# quadparts.net
KiCad netlist of a schematic drawn in EAGLE
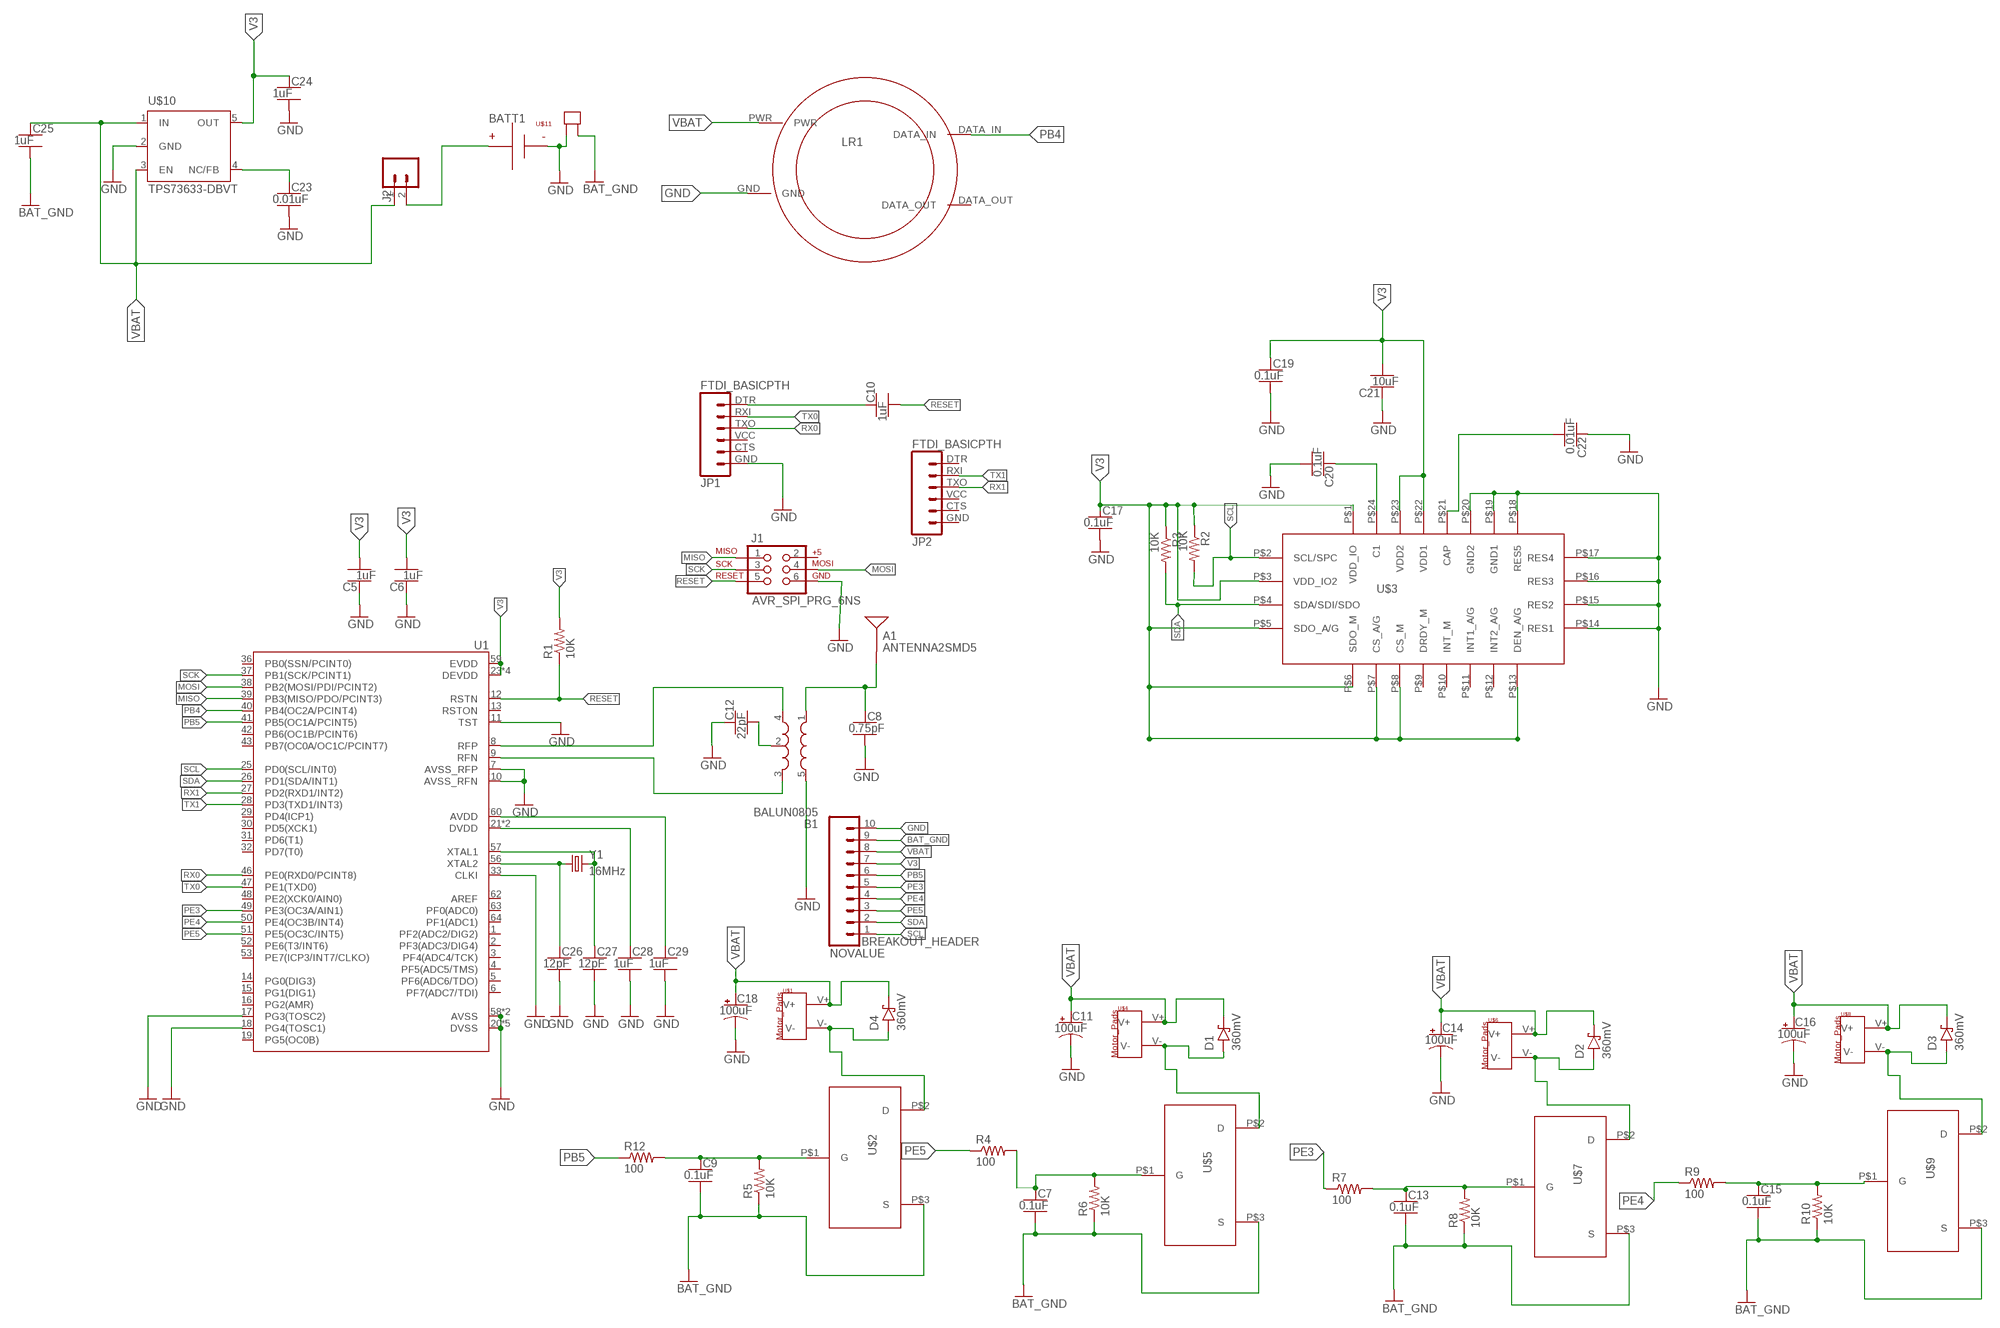
[diagram p0: schematic, sheet 1]

(export (version "E")
  (design (tool "Eeschema 10.0.6"))
  (components
    (comp (ref "A1")
      (value "ANTENNA2SMD5")
      (footprint "eagle-import:ANTENNA-CHIP5")
      (fields (field (name "MFR") "Linx Technologies Inc.") (field (name "MPN") "ANT-2.45-CHP-T"))
      (libsource (lib "eagle-import") (part "ANTENNA2SMD5"))
    )
    (comp (ref "B1")
      (value "BALUN0805")
      (footprint "eagle-import:BALUN")
      (fields (field (name "MFR") "Wurth Electronics Inc") (field (name "MPN") "748421245"))
      (libsource (lib "eagle-import") (part "BALUN0805"))
    )
    (comp (ref "BATT1")
      (value "BATTERY-HUBSAN-W/HOLDER")
      (footprint "eagle-import:BATTERY-W_HOLDER-380MAH-HUBSAN")
      (fields
        (field (name "MFR") "HUBSAN")
        (field (name "MPN") "X4-H107C-8-in-1")
        (field (name "CREATOR") "Swanson")
      )
      (libsource (lib "eagle-import") (part "BATTERY-HUBSAN-W/HOLDER"))
    )
    (comp (ref "BREAKOUT_HEADER")
      (value "NOVALUE")
      (footprint "eagle-import:HDRV10W63P254_10X1_2540X254H838_HS")
      (fields (field (name "MFR") "Amphenol FCI") (field (name "MPN") "68000-110HLF"))
      (libsource (lib "eagle-import") (part "SIP-10_TH-254X10"))
    )
    (comp (ref "C5")
      (value "1uF")
      (footprint "eagle-import:CAPC2012X140_HS")
      (fields
        (field (name "MFR") "Murata Electronics North America")
        (field (name "MPN") "GRM21BR71H105KA12L")
      )
      (libsource (lib "eagle-import") (part "CAPACITOR-NP_SMD-2012-0805_CERAMIC-1UF"))
    )
    (comp (ref "C6")
      (value "1uF")
      (footprint "eagle-import:CAPC2012X140_HS")
      (fields
        (field (name "MFR") "Murata Electronics North America")
        (field (name "MPN") "GRM21BR71H105KA12L")
      )
      (libsource (lib "eagle-import") (part "CAPACITOR-NP_SMD-2012-0805_CERAMIC-1UF"))
    )
    (comp (ref "C7")
      (value "0.1uF")
      (footprint "eagle-import:CERAMIC_CAP_0805")
      (fields
        (field (name "MFR") "Murata Electronics North America")
        (field (name "MPN") "GRM21BR71H104KA01L")
        (field (name "CREATOR") "SWANSON")
      )
      (libsource (lib "eagle-import") (part "CERAMIC_CAP-0805-0.1UF"))
    )
    (comp (ref "C8")
      (value "0.75pF")
      (footprint "eagle-import:CAPC2012X140_HS")
      (fields
        (field (name "MFR") "Murata Electronics North America")
        (field (name "MPN") "GQM2195C2AR75CB01D")
      )
      (libsource (lib "eagle-import") (part "CAPACITOR-NP_SMD-2012-0805_CERAMIC-0.75PF"))
    )
    (comp (ref "C9")
      (value "0.1uF")
      (footprint "eagle-import:CERAMIC_CAP_0805")
      (fields
        (field (name "MFR") "Murata Electronics North America")
        (field (name "MPN") "GRM21BR71H104KA01L")
        (field (name "CREATOR") "SWANSON")
      )
      (libsource (lib "eagle-import") (part "CERAMIC_CAP-0805-0.1UF"))
    )
    (comp (ref "C10")
      (value "1uF")
      (footprint "eagle-import:CAPC2012X140_HS")
      (fields
        (field (name "MFR") "Murata Electronics North America")
        (field (name "MPN") "GRM21BR71H105KA12L")
      )
      (libsource (lib "eagle-import") (part "CAPACITOR-NP_SMD-2012-0805_CERAMIC-1UF"))
    )
    (comp (ref "C11")
      (value "100uF")
      (footprint "eagle-import:CAPMP7343X310_HS")
      (fields (field (name "MFR") "AVX Corporation") (field (name "MPN") "TAJD227K006RNJ"))
      (libsource (lib "eagle-import") (part "CAPACITOR-POL_SMD-7043-D_TANTALUM-220UF"))
    )
    (comp (ref "C12")
      (value "22pF")
      (footprint "eagle-import:CAPC2012X140_HS")
      (fields
        (field (name "MFR") "Murata Electronics North America")
        (field (name "MPN") "GRM21A5C2E220JW01D")
      )
      (libsource (lib "eagle-import") (part "CAPACITOR-NP_SMD-2012-0805_CERAMIC-22PF"))
    )
    (comp (ref "C13")
      (value "0.1uF")
      (footprint "eagle-import:CERAMIC_CAP_0805")
      (fields
        (field (name "MFR") "Murata Electronics North America")
        (field (name "MPN") "GRM21BR71H104KA01L")
        (field (name "CREATOR") "SWANSON")
      )
      (libsource (lib "eagle-import") (part "CERAMIC_CAP-0805-0.1UF"))
    )
    (comp (ref "C14")
      (value "100uF")
      (footprint "eagle-import:CAPMP7343X310_HS")
      (fields (field (name "MFR") "AVX Corporation") (field (name "MPN") "TAJD227K006RNJ"))
      (libsource (lib "eagle-import") (part "CAPACITOR-POL_SMD-7043-D_TANTALUM-220UF"))
    )
    (comp (ref "C15")
      (value "0.1uF")
      (footprint "eagle-import:CERAMIC_CAP_0805")
      (fields
        (field (name "MFR") "Murata Electronics North America")
        (field (name "MPN") "GRM21BR71H104KA01L")
        (field (name "CREATOR") "SWANSON")
      )
      (libsource (lib "eagle-import") (part "CERAMIC_CAP-0805-0.1UF"))
    )
    (comp (ref "C16")
      (value "100uF")
      (footprint "eagle-import:CAPMP7343X310_HS")
      (fields (field (name "MFR") "AVX Corporation") (field (name "MPN") "TAJD227K006RNJ"))
      (libsource (lib "eagle-import") (part "CAPACITOR-POL_SMD-7043-D_TANTALUM-220UF"))
    )
    (comp (ref "C17")
      (value "0.1uF")
      (footprint "eagle-import:CAPC2012X140_HS")
      (fields
        (field (name "MFR") "Murata Electronics North America")
        (field (name "MPN") "GRM21BR71H104KA01L")
      )
      (libsource (lib "eagle-import") (part "CAPACITOR-NP_SMD-2012-0805_CERAMIC-0.1UF"))
    )
    (comp (ref "C18")
      (value "100uF")
      (footprint "eagle-import:CAPMP7343X310_HS")
      (fields (field (name "MFR") "AVX Corporation") (field (name "MPN") "TAJD227K006RNJ"))
      (libsource (lib "eagle-import") (part "CAPACITOR-POL_SMD-7043-D_TANTALUM-220UF"))
    )
    (comp (ref "C19")
      (value "0.1uF")
      (footprint "eagle-import:CAPC2012X140_HS")
      (fields
        (field (name "MFR") "Murata Electronics North America")
        (field (name "MPN") "GRM21BR71H104KA01L")
      )
      (libsource (lib "eagle-import") (part "CAPACITOR-NP_SMD-2012-0805_CERAMIC-0.1UF"))
    )
    (comp (ref "C20")
      (value "0.1uF")
      (footprint "eagle-import:CAPC2012X140_HS")
      (fields
        (field (name "MFR") "Murata Electronics North America")
        (field (name "MPN") "GRM21BR71H104KA01L")
      )
      (libsource (lib "eagle-import") (part "CAPACITOR-NP_SMD-2012-0805_CERAMIC-0.1UF"))
    )
    (comp (ref "C21")
      (value "10uF")
      (footprint "eagle-import:CAPC2012X140_HS")
      (fields
        (field (name "MFR") "Murata Electronics North America")
        (field (name "MPN") "GRM21BR61E106KA73L")
      )
      (libsource (lib "eagle-import") (part "CAPACITOR-NP_SMD-2012-0805_CERAMIC-10UF"))
    )
    (comp (ref "C22")
      (value "0.01uF")
      (footprint "eagle-import:CAPC2012X140_HS")
      (fields
        (field (name "MFR") "Murata Electronics North America")
        (field (name "MPN") "GRM2195C1H103FA01D")
      )
      (libsource (lib "eagle-import") (part "CAPACITOR-NP_SMD-2012-0805_CERAMIC-0.01UF"))
    )
    (comp (ref "C23")
      (value "0.01uF")
      (footprint "eagle-import:CAPC2012X140_HS")
      (fields
        (field (name "MFR") "Murata Electronics North America")
        (field (name "MPN") "GRM2195C1H103FA01D")
      )
      (libsource (lib "eagle-import") (part "CAPACITOR-NP_SMD-2012-0805_CERAMIC-0.01UF"))
    )
    (comp (ref "C24")
      (value "1uF")
      (footprint "eagle-import:CAPC2012X140_HS")
      (fields
        (field (name "MFR") "Murata Electronics North America")
        (field (name "MPN") "GRM21BR71H105KA12L")
      )
      (libsource (lib "eagle-import") (part "CAPACITOR-NP_SMD-2012-0805_CERAMIC-1UF"))
    )
    (comp (ref "C25")
      (value "1uF")
      (footprint "eagle-import:CAPC2012X140_HS")
      (fields
        (field (name "MFR") "Murata Electronics North America")
        (field (name "MPN") "GRM21BR71H105KA12L")
      )
      (libsource (lib "eagle-import") (part "CAPACITOR-NP_SMD-2012-0805_CERAMIC-1UF"))
    )
    (comp (ref "C26")
      (value "12pF")
      (footprint "eagle-import:CAPC2012X140_HS")
      (fields
        (field (name "MFR") "Murata Electronics North America")
        (field (name "MPN") "GRM21A5C2E120JW01D")
      )
      (libsource (lib "eagle-import") (part "CAPACITOR-NP_SMD-2012-0805_CERAMIC-12PF"))
    )
    (comp (ref "C27")
      (value "12pF")
      (footprint "eagle-import:CAPC2012X140_HS")
      (fields
        (field (name "MFR") "Murata Electronics North America")
        (field (name "MPN") "GRM21A5C2E120JW01D")
      )
      (libsource (lib "eagle-import") (part "CAPACITOR-NP_SMD-2012-0805_CERAMIC-12PF"))
    )
    (comp (ref "C28")
      (value "1uF")
      (footprint "eagle-import:CAPC2012X140_HS")
      (fields
        (field (name "MFR") "Murata Electronics North America")
        (field (name "MPN") "GRM21BR71H105KA12L")
      )
      (libsource (lib "eagle-import") (part "CAPACITOR-NP_SMD-2012-0805_CERAMIC-1UF"))
    )
    (comp (ref "C29")
      (value "1uF")
      (footprint "eagle-import:CAPC2012X140_HS")
      (fields
        (field (name "MFR") "Murata Electronics North America")
        (field (name "MPN") "GRM21BR71H105KA12L")
      )
      (libsource (lib "eagle-import") (part "CAPACITOR-NP_SMD-2012-0805_CERAMIC-1UF"))
    )
    (comp (ref "D1")
      (value "360mV")
      (footprint "eagle-import:SOD3716X135_HS")
      (fields
        (field (name "MFR") "Toshiba Semiconductor and Storage")
        (field (name "MPN") "CRS08(TE85L,Q,M)")
      )
      (libsource (lib "eagle-import") (part "DIODE-SCHOTTKY_SMD-SOD123-360MV"))
    )
    (comp (ref "D2")
      (value "360mV")
      (footprint "eagle-import:SOD3716X135_HS")
      (fields
        (field (name "MFR") "Toshiba Semiconductor and Storage")
        (field (name "MPN") "CRS08(TE85L,Q,M)")
      )
      (libsource (lib "eagle-import") (part "DIODE-SCHOTTKY_SMD-SOD123-360MV"))
    )
    (comp (ref "D3")
      (value "360mV")
      (footprint "eagle-import:SOD3716X135_HS")
      (fields
        (field (name "MFR") "Toshiba Semiconductor and Storage")
        (field (name "MPN") "CRS08(TE85L,Q,M)")
      )
      (libsource (lib "eagle-import") (part "DIODE-SCHOTTKY_SMD-SOD123-360MV"))
    )
    (comp (ref "D4")
      (value "360mV")
      (footprint "eagle-import:SOD3716X135_HS")
      (fields
        (field (name "MFR") "Toshiba Semiconductor and Storage")
        (field (name "MPN") "CRS08(TE85L,Q,M)")
      )
      (libsource (lib "eagle-import") (part "DIODE-SCHOTTKY_SMD-SOD123-360MV"))
    )
    (comp (ref "J1")
      (value "AVR_SPI_PRG_6NS")
      (footprint "eagle-import:2X3-NS")
      (fields (field (name "MFR") "Amphenol FCI") (field (name "MPN") "67997-206HLF"))
      (libsource (lib "eagle-import") (part "AVR_SPI_PRG_6NS"))
    )
    (comp (ref "J2")
      (value "MALE_HEADER_2POS-2X1-0.1IN")
      (footprint "eagle-import:MALE_HEADER_2X1_0.1IN")
      (fields
        (field (name "MFR") "3M")
        (field (name "MPN") "961102-6404-AR")
        (field (name "CREATOR") "SWANSON")
      )
      (libsource (lib "eagle-import") (part "MALE_HEADER_2POS-2X1-0.1IN"))
    )
    (comp (ref "JP1")
      (value "FTDI_BASICPTH")
      (footprint "eagle-import:FTDI_BASIC")
      (fields (field (name "MFR") "Amphenol FCI") (field (name "MPN") "68016-406HLF"))
      (libsource (lib "eagle-import") (part "FTDI_BASICPTH"))
    )
    (comp (ref "JP2")
      (value "FTDI_BASICPTH")
      (footprint "eagle-import:FTDI_BASIC")
      (fields (field (name "MFR") "Amphenol FCI") (field (name "MPN") "68016-406HLF"))
      (libsource (lib "eagle-import") (part "FTDI_BASICPTH"))
    )
    (comp (ref "LR1")
      (value "LED_RING")
      (footprint "eagle-import:LED_RING")
      (libsource (lib "eagle-import") (part "LED_RING"))
    )
    (comp (ref "R1")
      (value "10K")
      (footprint "eagle-import:RESC2012X60_HS")
      (fields (field (name "MFR") "Yageo") (field (name "MPN") "RC0805JR-0710KL"))
      (libsource (lib "eagle-import") (part "RESISTOR_SMD-2012-0805-10K"))
    )
    (comp (ref "R2")
      (value "10K")
      (footprint "eagle-import:RESC2012X60_HS")
      (fields (field (name "MFR") "Yageo") (field (name "MPN") "RC0805JR-0710KL"))
      (libsource (lib "eagle-import") (part "RESISTOR_SMD-2012-0805-10K"))
    )
    (comp (ref "R3")
      (value "10K")
      (footprint "eagle-import:RESC2012X60_HS")
      (fields (field (name "MFR") "Yageo") (field (name "MPN") "RC0805JR-0710KL"))
      (libsource (lib "eagle-import") (part "RESISTOR_SMD-2012-0805-10K"))
    )
    (comp (ref "R4")
      (value "100")
      (footprint "eagle-import:RESC2012X60_HS")
      (fields (field (name "MFR") "Yageo") (field (name "MPN") "RC0805JR-07100RL"))
      (libsource (lib "eagle-import") (part "RESISTOR_SMD-2012-0805-100"))
    )
    (comp (ref "R5")
      (value "10K")
      (footprint "eagle-import:RESC2012X60_HS")
      (fields (field (name "MFR") "Yageo") (field (name "MPN") "RC0805JR-0710KL"))
      (libsource (lib "eagle-import") (part "RESISTOR_SMD-2012-0805-10K"))
    )
    (comp (ref "R6")
      (value "10K")
      (footprint "eagle-import:RESC2012X60_HS")
      (fields (field (name "MFR") "Yageo") (field (name "MPN") "RC0805JR-0710KL"))
      (libsource (lib "eagle-import") (part "RESISTOR_SMD-2012-0805-10K"))
    )
    (comp (ref "R7")
      (value "100")
      (footprint "eagle-import:RESC2012X60_HS")
      (fields (field (name "MFR") "Yageo") (field (name "MPN") "RC0805JR-07100RL"))
      (libsource (lib "eagle-import") (part "RESISTOR_SMD-2012-0805-100"))
    )
    (comp (ref "R8")
      (value "10K")
      (footprint "eagle-import:RESC2012X60_HS")
      (fields (field (name "MFR") "Yageo") (field (name "MPN") "RC0805JR-0710KL"))
      (libsource (lib "eagle-import") (part "RESISTOR_SMD-2012-0805-10K"))
    )
    (comp (ref "R9")
      (value "100")
      (footprint "eagle-import:RESC2012X60_HS")
      (fields (field (name "MFR") "Yageo") (field (name "MPN") "RC0805JR-07100RL"))
      (libsource (lib "eagle-import") (part "RESISTOR_SMD-2012-0805-100"))
    )
    (comp (ref "R10")
      (value "10K")
      (footprint "eagle-import:RESC2012X60_HS")
      (fields (field (name "MFR") "Yageo") (field (name "MPN") "RC0805JR-0710KL"))
      (libsource (lib "eagle-import") (part "RESISTOR_SMD-2012-0805-10K"))
    )
    (comp (ref "R12")
      (value "100")
      (footprint "eagle-import:RESC2012X60_HS")
      (fields (field (name "MFR") "Yageo") (field (name "MPN") "RC0805JR-07100RL"))
      (libsource (lib "eagle-import") (part "RESISTOR_SMD-2012-0805-100"))
    )
    (comp (ref "U$1")
      (value "MOTOR_PADS")
      (footprint "eagle-import:MOTOR_PADS")
      (fields (field (name "MFR") "NA"))
      (libsource (lib "eagle-import") (part "MOTOR_PADS"))
    )
    (comp (ref "U$2")
      (value "N-CHANNEL_MOSFET")
      (footprint "eagle-import:N-CHANNELMOFSET")
      (fields
        (field (name "MFR") "Vishay Siliconix")
        (field (name "MPN") "SI2302CDS-T1-E3")
        (field (name "CREATOR") "Jason_Wong")
      )
      (libsource (lib "eagle-import") (part "N-CHANNEL_MOSFET"))
    )
    (comp (ref "U$3")
      (value "9-AXIS_IMU")
      (footprint "eagle-import:9-AXIS_IMU")
      (fields
        (field (name "MFR") "STMicroelectronics")
        (field (name "MPN") "LSM9DS1TR")
        (field (name "CREATOR") "Jason_Wong")
      )
      (libsource (lib "eagle-import") (part "9-AXIS_IMU"))
    )
    (comp (ref "U$4")
      (value "MOTOR_PADS")
      (footprint "eagle-import:MOTOR_PADS")
      (fields (field (name "MFR") "NA"))
      (libsource (lib "eagle-import") (part "MOTOR_PADS"))
    )
    (comp (ref "U$5")
      (value "N-CHANNEL_MOSFET")
      (footprint "eagle-import:N-CHANNELMOFSET")
      (fields
        (field (name "MFR") "Vishay Siliconix")
        (field (name "MPN") "SI2302CDS-T1-E3")
        (field (name "CREATOR") "Jason_Wong")
      )
      (libsource (lib "eagle-import") (part "N-CHANNEL_MOSFET"))
    )
    (comp (ref "U$6")
      (value "MOTOR_PADS")
      (footprint "eagle-import:MOTOR_PADS")
      (fields (field (name "MFR") "NA"))
      (libsource (lib "eagle-import") (part "MOTOR_PADS"))
    )
    (comp (ref "U$7")
      (value "N-CHANNEL_MOSFET")
      (footprint "eagle-import:N-CHANNELMOFSET")
      (fields
        (field (name "MFR") "Vishay Siliconix")
        (field (name "MPN") "SI2302CDS-T1-E3")
        (field (name "CREATOR") "Jason_Wong")
      )
      (libsource (lib "eagle-import") (part "N-CHANNEL_MOSFET"))
    )
    (comp (ref "U$8")
      (value "MOTOR_PADS")
      (footprint "eagle-import:MOTOR_PADS")
      (fields (field (name "MFR") "NA"))
      (libsource (lib "eagle-import") (part "MOTOR_PADS"))
    )
    (comp (ref "U$9")
      (value "N-CHANNEL_MOSFET")
      (footprint "eagle-import:N-CHANNELMOFSET")
      (fields
        (field (name "MFR") "Vishay Siliconix")
        (field (name "MPN") "SI2302CDS-T1-E3")
        (field (name "CREATOR") "Jason_Wong")
      )
      (libsource (lib "eagle-import") (part "N-CHANNEL_MOSFET"))
    )
    (comp (ref "U$10")
      (value "TPS73633-DBVT")
      (footprint "eagle-import:SOT23-DBV")
      (fields (field (name "MFR") "Texas Instruments") (field (name "MPN") "LP3985IM5X-3.0/NOPB"))
      (libsource (lib "eagle-import") (part "TPS73633-DBVT"))
    )
    (comp (ref "U$11")
      (value "NET_BRIDGE")
      (footprint "eagle-import:NET_BRIDGE")
      (libsource (lib "eagle-import") (part "NET_BRIDGE"))
    )
    (comp (ref "U1")
      (value "ATMEGA128RFA1")
      (footprint "eagle-import:QFN-64")
      (fields
        (field (name "MFR") "Atmel")
        (field (name "MPN") "ATMEGA128RFA1-ZUR00")
        (field (name "CREATOR") "Swanson")
      )
      (libsource (lib "eagle-import") (part "ATMEGA128RFA1"))
    )
    (comp (ref "Y1")
      (value "16MHz")
      (footprint "eagle-import:CRYSTAL-SMD-5X3")
      (fields (field (name "MFR") "Abracon LLC") (field (name "MPN") "ABM3B-16.000MHZ-B2-T"))
      (libsource (lib "eagle-import") (part "CRYSTAL5X3"))
    )
  )
  (nets
    (net (code "1") (name "BAT_GND") (class "Default")
      (node (ref "BREAKOUT_HEADER") (pin "9") (pinfunction "9_9") (pintype "passive"))
      (node (ref "C13") (pin "2") (pinfunction "2_2") (pintype "passive"))
      (node (ref "C15") (pin "2") (pinfunction "2_2") (pintype "passive"))
      (node (ref "C25") (pin "2") (pinfunction "2_2") (pintype "passive"))
      (node (ref "C7") (pin "2") (pinfunction "2_2") (pintype "passive"))
      (node (ref "C9") (pin "2") (pinfunction "2_2") (pintype "passive"))
      (node (ref "R10") (pin "1") (pinfunction "1_1") (pintype "passive"))
      (node (ref "R5") (pin "1") (pinfunction "1_1") (pintype "passive"))
      (node (ref "R6") (pin "1") (pinfunction "1_1") (pintype "passive"))
      (node (ref "R8") (pin "1") (pinfunction "1_1") (pintype "passive"))
      (node (ref "U$11") (pin "P$2") (pinfunction "P$2_P$2") (pintype "bidirectional"))
      (node (ref "U$2") (pin "P$3") (pinfunction "S_P$3") (pintype "bidirectional"))
      (node (ref "U$5") (pin "P$3") (pinfunction "S_P$3") (pintype "bidirectional"))
      (node (ref "U$7") (pin "P$3") (pinfunction "S_P$3") (pintype "bidirectional"))
      (node (ref "U$9") (pin "P$3") (pinfunction "S_P$3") (pintype "bidirectional"))
    )
    (net (code "2") (name "GND") (class "Default")
      (node (ref "B1") (pin "5") (pinfunction "GND_5") (pintype "bidirectional"))
      (node (ref "BATT1") (pin "-") (pinfunction "N_-") (pintype "bidirectional"))
      (node (ref "BREAKOUT_HEADER") (pin "10") (pinfunction "10_10") (pintype "passive"))
      (node (ref "C11") (pin "2") (pinfunction "-_2") (pintype "passive"))
      (node (ref "C12") (pin "1") (pinfunction "1_1") (pintype "passive"))
      (node (ref "C14") (pin "2") (pinfunction "-_2") (pintype "passive"))
      (node (ref "C16") (pin "2") (pinfunction "-_2") (pintype "passive"))
      (node (ref "C17") (pin "2") (pinfunction "2_2") (pintype "passive"))
      (node (ref "C18") (pin "2") (pinfunction "-_2") (pintype "passive"))
      (node (ref "C19") (pin "2") (pinfunction "2_2") (pintype "passive"))
      (node (ref "C20") (pin "2") (pinfunction "2_2") (pintype "passive"))
      (node (ref "C21") (pin "1") (pinfunction "1_1") (pintype "passive"))
      (node (ref "C22") (pin "1") (pinfunction "1_1") (pintype "passive"))
      (node (ref "C23") (pin "2") (pinfunction "2_2") (pintype "passive"))
      (node (ref "C24") (pin "2") (pinfunction "2_2") (pintype "passive"))
      (node (ref "C26") (pin "2") (pinfunction "2_2") (pintype "passive"))
      (node (ref "C27") (pin "2") (pinfunction "2_2") (pintype "passive"))
      (node (ref "C28") (pin "2") (pinfunction "2_2") (pintype "passive"))
      (node (ref "C29") (pin "2") (pinfunction "2_2") (pintype "passive"))
      (node (ref "C5") (pin "1") (pinfunction "1_1") (pintype "passive"))
      (node (ref "C6") (pin "1") (pinfunction "1_1") (pintype "passive"))
      (node (ref "C8") (pin "2") (pinfunction "2_2") (pintype "passive"))
      (node (ref "J1") (pin "6") (pinfunction "6_6") (pintype "passive"))
      (node (ref "JP1") (pin "GND") (pinfunction "6_GND") (pintype "passive"))
      (node (ref "LR1") (pin "GND") (pinfunction "GND_GND") (pintype "bidirectional"))
      (node (ref "U$10") (pin "2") (pinfunction "GND_2") (pintype "input"))
      (node (ref "U$11") (pin "P$1") (pinfunction "P$1_P$1") (pintype "bidirectional"))
      (node (ref "U$3") (pin "P$14") (pinfunction "RES1_P$14") (pintype "bidirectional"))
      (node (ref "U$3") (pin "P$15") (pinfunction "RES2_P$15") (pintype "bidirectional"))
      (node (ref "U$3") (pin "P$16") (pinfunction "RES3_P$16") (pintype "bidirectional"))
      (node (ref "U$3") (pin "P$17") (pinfunction "RES4_P$17") (pintype "bidirectional"))
      (node (ref "U$3") (pin "P$18") (pinfunction "RES5_P$18") (pintype "bidirectional"))
      (node (ref "U$3") (pin "P$19") (pinfunction "GND1_P$19") (pintype "bidirectional"))
      (node (ref "U$3") (pin "P$20") (pinfunction "GND2_P$20") (pintype "bidirectional"))
      (node (ref "U1") (pin "10") (pinfunction "AVSS_RFN_10") (pintype "bidirectional"))
      (node (ref "U1") (pin "11") (pinfunction "TST_11") (pintype "bidirectional"))
      (node (ref "U1") (pin "17") (pinfunction "PG3(TOSC2)_17") (pintype "bidirectional"))
      (node (ref "U1") (pin "18") (pinfunction "PG4(TOSC1)_18") (pintype "bidirectional"))
      (node (ref "U1") (pin "20") (pinfunction "DVSS_20") (pintype "bidirectional"))
      (node (ref "U1") (pin "24") (pinfunction "DVSS_24") (pintype "bidirectional"))
      (node (ref "U1") (pin "33") (pinfunction "CLKI_33") (pintype "bidirectional"))
      (node (ref "U1") (pin "35") (pinfunction "DVSS_35") (pintype "bidirectional"))
      (node (ref "U1") (pin "45") (pinfunction "DVSS_45") (pintype "bidirectional"))
      (node (ref "U1") (pin "55") (pinfunction "DVSS_55") (pintype "bidirectional"))
      (node (ref "U1") (pin "58") (pinfunction "AVSS_58") (pintype "bidirectional"))
      (node (ref "U1") (pin "61") (pinfunction "AVSS_61") (pintype "bidirectional"))
      (node (ref "U1") (pin "7") (pinfunction "AVSS_RFP_7") (pintype "bidirectional"))
    )
    (net (code "3") (name "MISO") (class "Default")
      (node (ref "J1") (pin "1") (pinfunction "1_1") (pintype "passive"))
      (node (ref "U1") (pin "39") (pinfunction "PB3(MISO/PDO/PCINT3)_39") (pintype "bidirectional"))
    )
    (net (code "4") (name "MOSI") (class "Default")
      (node (ref "J1") (pin "4") (pinfunction "4_4") (pintype "passive"))
      (node (ref "U1") (pin "38") (pinfunction "PB2(MOSI/PDI/PCINT2)_38") (pintype "bidirectional"))
    )
    (net (code "5") (name "Net-(A1-SIGNAL)") (class "Default")
      (node (ref "A1") (pin "FEED") (pinfunction "SIGNAL_FEED") (pintype "bidirectional"))
      (node (ref "B1") (pin "1") (pinfunction "IN_1") (pintype "bidirectional"))
      (node (ref "C8") (pin "1") (pinfunction "1_1") (pintype "passive"))
    )
    (net (code "6") (name "Net-(B1-GND-Pad2)") (class "Default")
      (node (ref "B1") (pin "2") (pinfunction "GND_2") (pintype "bidirectional"))
      (node (ref "C12") (pin "2") (pinfunction "2_2") (pintype "passive"))
    )
    (net (code "7") (name "Net-(B1-OUT1)") (class "Default")
      (node (ref "B1") (pin "4") (pinfunction "OUT1_4") (pintype "bidirectional"))
      (node (ref "U1") (pin "8") (pinfunction "RFP_8") (pintype "bidirectional"))
    )
    (net (code "8") (name "Net-(B1-OUT2)") (class "Default")
      (node (ref "B1") (pin "3") (pinfunction "OUT2_3") (pintype "bidirectional"))
      (node (ref "U1") (pin "9") (pinfunction "RFN_9") (pintype "bidirectional"))
    )
    (net (code "9") (name "Net-(BATT1-P)") (class "Default")
      (node (ref "BATT1") (pin "+") (pinfunction "P_+") (pintype "bidirectional"))
      (node (ref "J2") (pin "2") (pinfunction "2_2") (pintype "passive"))
    )
    (net (code "10") (name "Net-(C16-+)") (class "Default")
      (node (ref "C16") (pin "1") (pinfunction "+_1") (pintype "passive"))
      (node (ref "D3") (pin "C") (pinfunction "C_C") (pintype "passive"))
      (node (ref "U$8") (pin "V+") (pinfunction "V+_V+") (pintype "bidirectional"))
    )
    (net (code "11") (name "Net-(C28-Pad1)") (class "Default")
      (node (ref "C28") (pin "1") (pinfunction "1_1") (pintype "passive"))
      (node (ref "U1") (pin "21") (pinfunction "DVDD_21") (pintype "bidirectional"))
      (node (ref "U1") (pin "22") (pinfunction "DVDD_22") (pintype "bidirectional"))
    )
    (net (code "12") (name "Net-(JP1-1)") (class "Default")
      (node (ref "C10") (pin "1") (pinfunction "1_1") (pintype "passive"))
      (node (ref "JP1") (pin "DTR") (pinfunction "1_DTR") (pintype "passive"))
    )
    (net (code "13") (name "Net-(U$2-D)") (class "Default")
      (node (ref "D4") (pin "A") (pinfunction "A_A") (pintype "passive"))
      (node (ref "U$1") (pin "V-") (pinfunction "V-_V-") (pintype "bidirectional"))
      (node (ref "U$2") (pin "P$2") (pinfunction "D_P$2") (pintype "bidirectional"))
    )
    (net (code "14") (name "Net-(U$2-G)") (class "Default")
      (node (ref "C9") (pin "1") (pinfunction "1_1") (pintype "passive"))
      (node (ref "R12") (pin "2") (pinfunction "2_2") (pintype "passive"))
      (node (ref "R5") (pin "2") (pinfunction "2_2") (pintype "passive"))
      (node (ref "U$2") (pin "P$1") (pinfunction "G_P$1") (pintype "bidirectional"))
    )
    (net (code "15") (name "Net-(U$3-C1)") (class "Default")
      (node (ref "C20") (pin "1") (pinfunction "1_1") (pintype "passive"))
      (node (ref "U$3") (pin "P$24") (pinfunction "C1_P$24") (pintype "bidirectional"))
    )
    (net (code "16") (name "Net-(U$3-CAP)") (class "Default")
      (node (ref "C22") (pin "2") (pinfunction "2_2") (pintype "passive"))
      (node (ref "U$3") (pin "P$21") (pinfunction "CAP_P$21") (pintype "bidirectional"))
    )
    (net (code "17") (name "Net-(U$5-D)") (class "Default")
      (node (ref "D1") (pin "A") (pinfunction "A_A") (pintype "passive"))
      (node (ref "U$4") (pin "V-") (pinfunction "V-_V-") (pintype "bidirectional"))
      (node (ref "U$5") (pin "P$2") (pinfunction "D_P$2") (pintype "bidirectional"))
    )
    (net (code "18") (name "Net-(U$5-G)") (class "Default")
      (node (ref "C7") (pin "1") (pinfunction "1_1") (pintype "passive"))
      (node (ref "R4") (pin "2") (pinfunction "2_2") (pintype "passive"))
      (node (ref "R6") (pin "2") (pinfunction "2_2") (pintype "passive"))
      (node (ref "U$5") (pin "P$1") (pinfunction "G_P$1") (pintype "bidirectional"))
    )
    (net (code "19") (name "Net-(U$7-D)") (class "Default")
      (node (ref "D2") (pin "A") (pinfunction "A_A") (pintype "passive"))
      (node (ref "U$6") (pin "V-") (pinfunction "V-_V-") (pintype "bidirectional"))
      (node (ref "U$7") (pin "P$2") (pinfunction "D_P$2") (pintype "bidirectional"))
    )
    (net (code "20") (name "Net-(U$7-G)") (class "Default")
      (node (ref "C13") (pin "1") (pinfunction "1_1") (pintype "passive"))
      (node (ref "R7") (pin "2") (pinfunction "2_2") (pintype "passive"))
      (node (ref "R8") (pin "2") (pinfunction "2_2") (pintype "passive"))
      (node (ref "U$7") (pin "P$1") (pinfunction "G_P$1") (pintype "bidirectional"))
    )
    (net (code "21") (name "Net-(U$9-D)") (class "Default")
      (node (ref "D3") (pin "A") (pinfunction "A_A") (pintype "passive"))
      (node (ref "U$8") (pin "V-") (pinfunction "V-_V-") (pintype "bidirectional"))
      (node (ref "U$9") (pin "P$2") (pinfunction "D_P$2") (pintype "bidirectional"))
    )
    (net (code "22") (name "Net-(U$9-G)") (class "Default")
      (node (ref "C15") (pin "1") (pinfunction "1_1") (pintype "passive"))
      (node (ref "R10") (pin "2") (pinfunction "2_2") (pintype "passive"))
      (node (ref "R9") (pin "2") (pinfunction "2_2") (pintype "passive"))
      (node (ref "U$9") (pin "P$1") (pinfunction "G_P$1") (pintype "bidirectional"))
    )
    (net (code "23") (name "Net-(U$10-NC{slash}FB)") (class "Default")
      (node (ref "C23") (pin "1") (pinfunction "1_1") (pintype "passive"))
      (node (ref "U$10") (pin "4") (pinfunction "NC/FB_4") (pintype "passive"))
    )
    (net (code "24") (name "Net-(U1-AVDD)") (class "Default")
      (node (ref "C29") (pin "1") (pinfunction "1_1") (pintype "passive"))
      (node (ref "U1") (pin "60") (pinfunction "AVDD_60") (pintype "bidirectional"))
    )
    (net (code "25") (name "Net-(U1-XTAL1)") (class "Default")
      (node (ref "C27") (pin "1") (pinfunction "1_1") (pintype "passive"))
      (node (ref "U1") (pin "57") (pinfunction "XTAL1_57") (pintype "bidirectional"))
      (node (ref "Y1") (pin "3") (pinfunction "2_3") (pintype "passive"))
    )
    (net (code "26") (name "Net-(U1-XTAL2)") (class "Default")
      (node (ref "C26") (pin "1") (pinfunction "1_1") (pintype "passive"))
      (node (ref "U1") (pin "56") (pinfunction "XTAL2_56") (pintype "bidirectional"))
      (node (ref "Y1") (pin "1") (pinfunction "1_1") (pintype "passive"))
    )
    (net (code "27") (name "PB4") (class "Default")
      (node (ref "LR1") (pin "DATA_IN") (pinfunction "DATA_IN_DATA_IN") (pintype "bidirectional"))
      (node (ref "U1") (pin "40") (pinfunction "PB4(OC2A/PCINT4)_40") (pintype "bidirectional"))
    )
    (net (code "28") (name "PB5") (class "Default")
      (node (ref "BREAKOUT_HEADER") (pin "6") (pinfunction "6_6") (pintype "passive"))
      (node (ref "R12") (pin "1") (pinfunction "1_1") (pintype "passive"))
      (node (ref "U1") (pin "41") (pinfunction "PB5(OC1A/PCINT5)_41") (pintype "bidirectional"))
    )
    (net (code "29") (name "PE3") (class "Default")
      (node (ref "BREAKOUT_HEADER") (pin "5") (pinfunction "5_5") (pintype "passive"))
      (node (ref "R7") (pin "1") (pinfunction "1_1") (pintype "passive"))
      (node (ref "U1") (pin "49") (pinfunction "PE3(OC3A/AIN1)_49") (pintype "bidirectional"))
    )
    (net (code "30") (name "PE4") (class "Default")
      (node (ref "BREAKOUT_HEADER") (pin "4") (pinfunction "4_4") (pintype "passive"))
      (node (ref "R9") (pin "1") (pinfunction "1_1") (pintype "passive"))
      (node (ref "U1") (pin "50") (pinfunction "PE4(OC3B/INT4)_50") (pintype "bidirectional"))
    )
    (net (code "31") (name "PE5") (class "Default")
      (node (ref "BREAKOUT_HEADER") (pin "3") (pinfunction "3_3") (pintype "passive"))
      (node (ref "R4") (pin "1") (pinfunction "1_1") (pintype "passive"))
      (node (ref "U1") (pin "51") (pinfunction "PE5(OC3C/INT5)_51") (pintype "bidirectional"))
    )
    (net (code "32") (name "RESET") (class "Default")
      (node (ref "C10") (pin "2") (pinfunction "2_2") (pintype "passive"))
      (node (ref "J1") (pin "5") (pinfunction "5_5") (pintype "passive"))
      (node (ref "R1") (pin "1") (pinfunction "1_1") (pintype "passive"))
      (node (ref "U1") (pin "12") (pinfunction "RSTN_12") (pintype "bidirectional"))
    )
    (net (code "33") (name "RX0") (class "Default")
      (node (ref "JP1") (pin "TXO") (pinfunction "3_TXO") (pintype "passive"))
      (node (ref "U1") (pin "46") (pinfunction "PE0(RXD0/PCINT8)_46") (pintype "bidirectional"))
    )
    (net (code "34") (name "RX1") (class "Default")
      (node (ref "JP2") (pin "TXO") (pinfunction "3_TXO") (pintype "passive"))
      (node (ref "U1") (pin "27") (pinfunction "PD2(RXD1/INT2)_27") (pintype "bidirectional"))
    )
    (net (code "35") (name "SCK") (class "Default")
      (node (ref "J1") (pin "3") (pinfunction "3_3") (pintype "passive"))
      (node (ref "U1") (pin "37") (pinfunction "PB1(SCK/PCINT1)_37") (pintype "bidirectional"))
    )
    (net (code "36") (name "SCL") (class "Default")
      (node (ref "BREAKOUT_HEADER") (pin "1") (pinfunction "1_1") (pintype "passive"))
      (node (ref "R2") (pin "2") (pinfunction "2_2") (pintype "passive"))
      (node (ref "U$3") (pin "P$2") (pinfunction "SCL/SPC_P$2") (pintype "bidirectional"))
      (node (ref "U1") (pin "25") (pinfunction "PD0(SCL/INT0)_25") (pintype "bidirectional"))
    )
    (net (code "37") (name "SDA") (class "Default")
      (node (ref "BREAKOUT_HEADER") (pin "2") (pinfunction "2_2") (pintype "passive"))
      (node (ref "R3") (pin "2") (pinfunction "2_2") (pintype "passive"))
      (node (ref "U$3") (pin "P$4") (pinfunction "SDA/SDI/SDO_P$4") (pintype "bidirectional"))
      (node (ref "U1") (pin "26") (pinfunction "PD1(SDA/INT1)_26") (pintype "bidirectional"))
    )
    (net (code "38") (name "TX0") (class "Default")
      (node (ref "JP1") (pin "RXI") (pinfunction "2_RXI") (pintype "passive"))
      (node (ref "U1") (pin "47") (pinfunction "PE1(TXD0)_47") (pintype "bidirectional"))
    )
    (net (code "39") (name "TX1") (class "Default")
      (node (ref "JP2") (pin "RXI") (pinfunction "2_RXI") (pintype "passive"))
      (node (ref "U1") (pin "28") (pinfunction "PD3(TXD1/INT3)_28") (pintype "bidirectional"))
    )
    (net (code "40") (name "V3") (class "Default")
      (node (ref "BREAKOUT_HEADER") (pin "7") (pinfunction "7_7") (pintype "passive"))
      (node (ref "C17") (pin "1") (pinfunction "1_1") (pintype "passive"))
      (node (ref "C19") (pin "1") (pinfunction "1_1") (pintype "passive"))
      (node (ref "C21") (pin "2") (pinfunction "2_2") (pintype "passive"))
      (node (ref "C24") (pin "1") (pinfunction "1_1") (pintype "passive"))
      (node (ref "C5") (pin "2") (pinfunction "2_2") (pintype "passive"))
      (node (ref "C6") (pin "2") (pinfunction "2_2") (pintype "passive"))
      (node (ref "R1") (pin "2") (pinfunction "2_2") (pintype "passive"))
      (node (ref "R2") (pin "1") (pinfunction "1_1") (pintype "passive"))
      (node (ref "R3") (pin "1") (pinfunction "1_1") (pintype "passive"))
      (node (ref "U$10") (pin "5") (pinfunction "OUT_5") (pintype "passive"))
      (node (ref "U$3") (pin "P$1") (pinfunction "VDD_IO_P$1") (pintype "bidirectional"))
      (node (ref "U$3") (pin "P$13") (pinfunction "DEN_A/G_P$13") (pintype "bidirectional"))
      (node (ref "U$3") (pin "P$22") (pinfunction "VDD1_P$22") (pintype "bidirectional"))
      (node (ref "U$3") (pin "P$23") (pinfunction "VDD2_P$23") (pintype "bidirectional"))
      (node (ref "U$3") (pin "P$3") (pinfunction "VDD_IO2_P$3") (pintype "bidirectional"))
      (node (ref "U$3") (pin "P$5") (pinfunction "SDO_A/G_P$5") (pintype "bidirectional"))
      (node (ref "U$3") (pin "P$6") (pinfunction "SDO_M_P$6") (pintype "bidirectional"))
      (node (ref "U$3") (pin "P$7") (pinfunction "CS_A/G_P$7") (pintype "bidirectional"))
      (node (ref "U$3") (pin "P$8") (pinfunction "CS_M_P$8") (pintype "bidirectional"))
      (node (ref "U1") (pin "23") (pinfunction "DEVDD_23") (pintype "bidirectional"))
      (node (ref "U1") (pin "34") (pinfunction "DEVDD_34") (pintype "bidirectional"))
      (node (ref "U1") (pin "44") (pinfunction "DEVDD_44") (pintype "bidirectional"))
      (node (ref "U1") (pin "54") (pinfunction "DEVDD_54") (pintype "bidirectional"))
      (node (ref "U1") (pin "59") (pinfunction "EVDD_59") (pintype "bidirectional"))
    )
    (net (code "41") (name "VBAT") (class "Default")
      (node (ref "BREAKOUT_HEADER") (pin "8") (pinfunction "8_8") (pintype "passive"))
      (node (ref "C11") (pin "1") (pinfunction "+_1") (pintype "passive"))
      (node (ref "C14") (pin "1") (pinfunction "+_1") (pintype "passive"))
      (node (ref "C18") (pin "1") (pinfunction "+_1") (pintype "passive"))
      (node (ref "C25") (pin "1") (pinfunction "1_1") (pintype "passive"))
      (node (ref "D1") (pin "C") (pinfunction "C_C") (pintype "passive"))
      (node (ref "D2") (pin "C") (pinfunction "C_C") (pintype "passive"))
      (node (ref "D4") (pin "C") (pinfunction "C_C") (pintype "passive"))
      (node (ref "J2") (pin "1") (pinfunction "1_1") (pintype "passive"))
      (node (ref "LR1") (pin "PWR") (pinfunction "PWR_PWR") (pintype "bidirectional"))
      (node (ref "U$1") (pin "V+") (pinfunction "V+_V+") (pintype "bidirectional"))
      (node (ref "U$10") (pin "1") (pinfunction "IN_1") (pintype "input"))
      (node (ref "U$10") (pin "3") (pinfunction "EN_3") (pintype "input"))
      (node (ref "U$4") (pin "V+") (pinfunction "V+_V+") (pintype "bidirectional"))
      (node (ref "U$6") (pin "V+") (pinfunction "V+_V+") (pintype "bidirectional"))
    )
    (net (code "42") (name "unconnected-(J1-Pad2)") (class "Default")
      (node (ref "J1") (pin "2") (pinfunction "2_2") (pintype "passive"))
    )
    (net (code "43") (name "unconnected-(JP1-4-PadVCC)") (class "Default")
      (node (ref "JP1") (pin "VCC") (pinfunction "4_VCC") (pintype "passive"))
    )
    (net (code "44") (name "unconnected-(JP1-5-PadCTS)") (class "Default")
      (node (ref "JP1") (pin "CTS") (pinfunction "5_CTS") (pintype "passive"))
    )
    (net (code "45") (name "unconnected-(JP2-1-PadDTR)") (class "Default")
      (node (ref "JP2") (pin "DTR") (pinfunction "1_DTR") (pintype "passive"))
    )
    (net (code "46") (name "unconnected-(JP2-4-PadVCC)") (class "Default")
      (node (ref "JP2") (pin "VCC") (pinfunction "4_VCC") (pintype "passive"))
    )
    (net (code "47") (name "unconnected-(JP2-5-PadCTS)") (class "Default")
      (node (ref "JP2") (pin "CTS") (pinfunction "5_CTS") (pintype "passive"))
    )
    (net (code "48") (name "unconnected-(JP2-6-PadGND)") (class "Default")
      (node (ref "JP2") (pin "GND") (pinfunction "6_GND") (pintype "passive"))
    )
    (net (code "49") (name "unconnected-(LR1-PadDATA_OUT)") (class "Default")
      (node (ref "LR1") (pin "DATA_OUT") (pinfunction "DATA_OUT_DATA_OUT") (pintype "bidirectional"))
    )
    (net (code "50") (name "unconnected-(U$3-DRDY_M-PadP$9)") (class "Default")
      (node (ref "U$3") (pin "P$9") (pinfunction "DRDY_M_P$9") (pintype "bidirectional"))
    )
    (net (code "51") (name "unconnected-(U$3-INT1_A{slash}G-PadP$11)") (class "Default")
      (node (ref "U$3") (pin "P$11") (pinfunction "INT1_A/G_P$11") (pintype "bidirectional"))
    )
    (net (code "52") (name "unconnected-(U$3-INT2_A{slash}G-PadP$12)") (class "Default")
      (node (ref "U$3") (pin "P$12") (pinfunction "INT2_A/G_P$12") (pintype "bidirectional"))
    )
    (net (code "53") (name "unconnected-(U$3-INT_M-PadP$10)") (class "Default")
      (node (ref "U$3") (pin "P$10") (pinfunction "INT_M_P$10") (pintype "bidirectional"))
    )
    (net (code "54") (name "unconnected-(U1-AREF-Pad62)") (class "Default")
      (node (ref "U1") (pin "62") (pinfunction "AREF_62") (pintype "bidirectional"))
    )
    (net (code "55") (name "unconnected-(U1-PB0(SSN{slash}PCINT0)-Pad36)") (class "Default")
      (node (ref "U1") (pin "36") (pinfunction "PB0(SSN/PCINT0)_36") (pintype "bidirectional"))
    )
    (net (code "56") (name "unconnected-(U1-PB6(OC1B{slash}PCINT6)-Pad42)") (class "Default")
      (node (ref "U1") (pin "42") (pinfunction "PB6(OC1B/PCINT6)_42") (pintype "bidirectional"))
    )
    (net (code "57") (name "unconnected-(U1-PB7(OC0A{slash}OC1C{slash}PCINT7)-Pad43)") (class "Default")
      (node (ref "U1") (pin "43") (pinfunction "PB7(OC0A/OC1C/PCINT7)_43") (pintype "bidirectional"))
    )
    (net (code "58") (name "unconnected-(U1-PD4(ICP1)-Pad29)") (class "Default")
      (node (ref "U1") (pin "29") (pinfunction "PD4(ICP1)_29") (pintype "bidirectional"))
    )
    (net (code "59") (name "unconnected-(U1-PD5(XCK1)-Pad30)") (class "Default")
      (node (ref "U1") (pin "30") (pinfunction "PD5(XCK1)_30") (pintype "bidirectional"))
    )
    (net (code "60") (name "unconnected-(U1-PD6(T1)-Pad31)") (class "Default")
      (node (ref "U1") (pin "31") (pinfunction "PD6(T1)_31") (pintype "bidirectional"))
    )
    (net (code "61") (name "unconnected-(U1-PD7(T0)-Pad32)") (class "Default")
      (node (ref "U1") (pin "32") (pinfunction "PD7(T0)_32") (pintype "bidirectional"))
    )
    (net (code "62") (name "unconnected-(U1-PE2(XCK0{slash}AIN0)-Pad48)") (class "Default")
      (node (ref "U1") (pin "48") (pinfunction "PE2(XCK0/AIN0)_48") (pintype "bidirectional"))
    )
    (net (code "63") (name "unconnected-(U1-PE6(T3{slash}INT6)-Pad52)") (class "Default")
      (node (ref "U1") (pin "52") (pinfunction "PE6(T3/INT6)_52") (pintype "bidirectional"))
    )
    (net (code "64") (name "unconnected-(U1-PE7(ICP3{slash}INT7{slash}CLKO)-Pad53)") (class "Default")
      (node (ref "U1") (pin "53") (pinfunction "PE7(ICP3/INT7/CLKO)_53") (pintype "bidirectional"))
    )
    (net (code "65") (name "unconnected-(U1-PF0(ADC0)-Pad63)") (class "Default")
      (node (ref "U1") (pin "63") (pinfunction "PF0(ADC0)_63") (pintype "bidirectional"))
    )
    (net (code "66") (name "unconnected-(U1-PF1(ADC1)-Pad64)") (class "Default")
      (node (ref "U1") (pin "64") (pinfunction "PF1(ADC1)_64") (pintype "bidirectional"))
    )
    (net (code "67") (name "unconnected-(U1-PF2(ADC2{slash}DIG2)-Pad1)") (class "Default")
      (node (ref "U1") (pin "1") (pinfunction "PF2(ADC2/DIG2)_1") (pintype "bidirectional"))
    )
    (net (code "68") (name "unconnected-(U1-PF3(ADC3{slash}DIG4)-Pad2)") (class "Default")
      (node (ref "U1") (pin "2") (pinfunction "PF3(ADC3/DIG4)_2") (pintype "bidirectional"))
    )
    (net (code "69") (name "unconnected-(U1-PF4(ADC4{slash}TCK)-Pad3)") (class "Default")
      (node (ref "U1") (pin "3") (pinfunction "PF4(ADC4/TCK)_3") (pintype "bidirectional"))
    )
    (net (code "70") (name "unconnected-(U1-PF5(ADC5{slash}TMS)-Pad4)") (class "Default")
      (node (ref "U1") (pin "4") (pinfunction "PF5(ADC5/TMS)_4") (pintype "bidirectional"))
    )
    (net (code "71") (name "unconnected-(U1-PF6(ADC6{slash}TDO)-Pad5)") (class "Default")
      (node (ref "U1") (pin "5") (pinfunction "PF6(ADC6/TDO)_5") (pintype "bidirectional"))
    )
    (net (code "72") (name "unconnected-(U1-PF7(ADC7{slash}TDI)-Pad6)") (class "Default")
      (node (ref "U1") (pin "6") (pinfunction "PF7(ADC7/TDI)_6") (pintype "bidirectional"))
    )
    (net (code "73") (name "unconnected-(U1-PG0(DIG3)-Pad14)") (class "Default")
      (node (ref "U1") (pin "14") (pinfunction "PG0(DIG3)_14") (pintype "bidirectional"))
    )
    (net (code "74") (name "unconnected-(U1-PG1(DIG1)-Pad15)") (class "Default")
      (node (ref "U1") (pin "15") (pinfunction "PG1(DIG1)_15") (pintype "bidirectional"))
    )
    (net (code "75") (name "unconnected-(U1-PG2(AMR)-Pad16)") (class "Default")
      (node (ref "U1") (pin "16") (pinfunction "PG2(AMR)_16") (pintype "bidirectional"))
    )
    (net (code "76") (name "unconnected-(U1-PG5(OC0B)-Pad19)") (class "Default")
      (node (ref "U1") (pin "19") (pinfunction "PG5(OC0B)_19") (pintype "bidirectional"))
    )
    (net (code "77") (name "unconnected-(U1-RSTON-Pad13)") (class "Default")
      (node (ref "U1") (pin "13") (pinfunction "RSTON_13") (pintype "bidirectional"))
    )
  )
)
